# SH3_-_MCU.net
KiCad netlist of a schematic drawn in Altium Designer
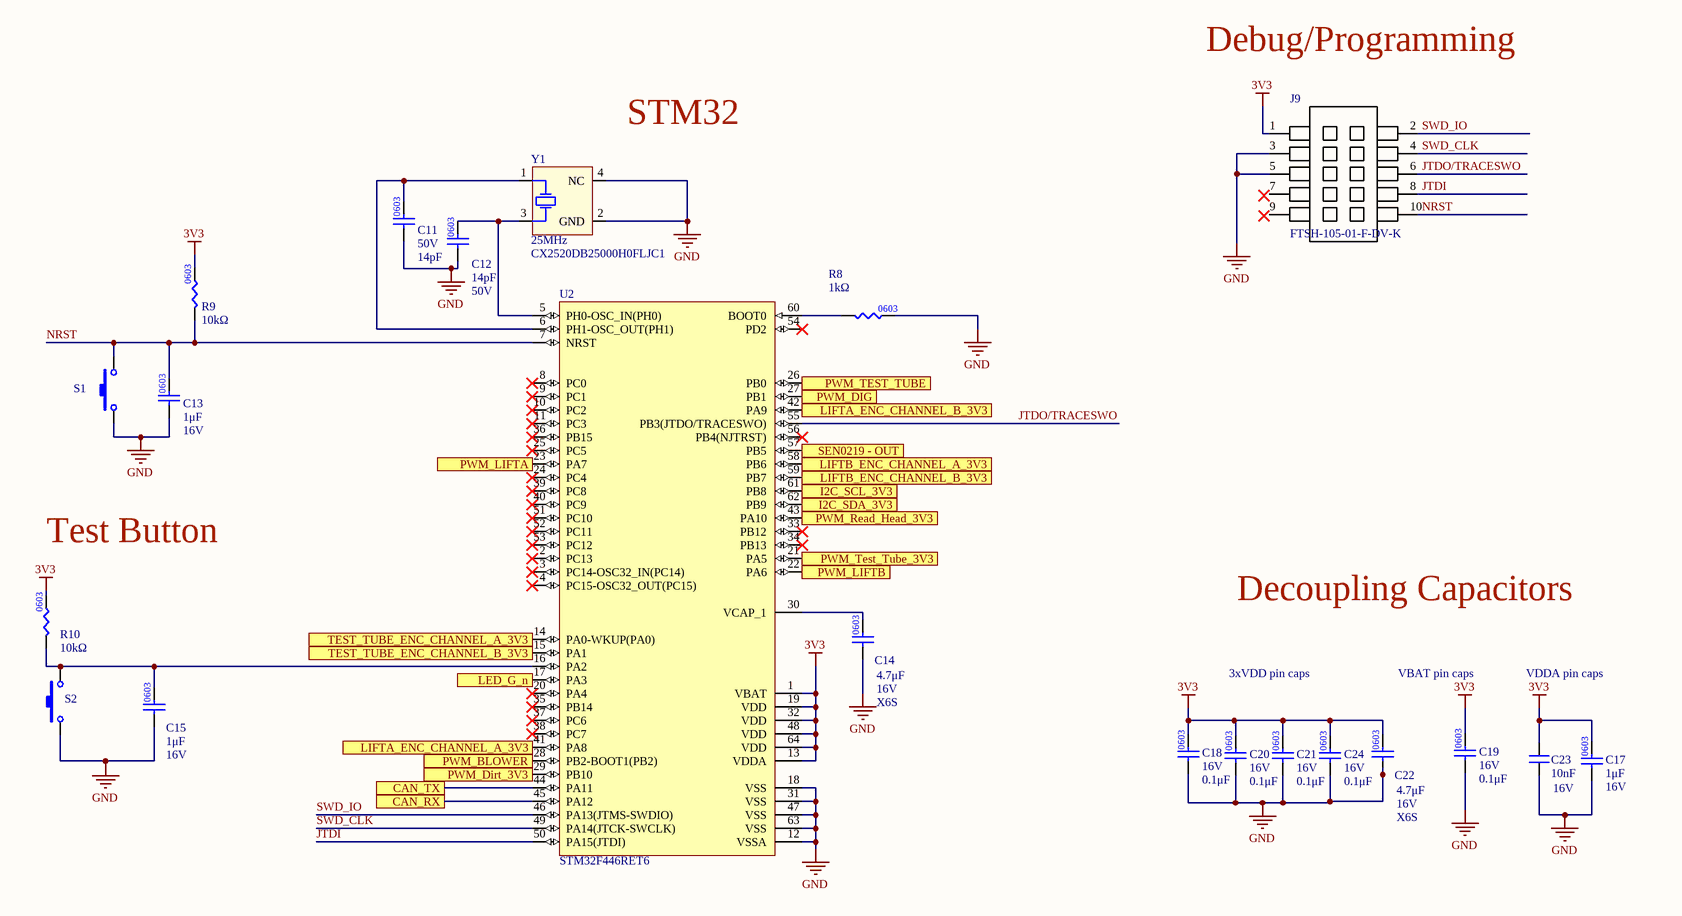
[diagram p0: SH3 - MCU.SchDoc]

(export (version "E")
  (design (tool "Eeschema 10.0.6"))
  (components
    (comp (ref "C11")
      (value "14pF")
      (footprint "CAP0603")
      (description "CAP CER 14PF 50V C0G/NP0 0603")
      (fields (field (name "VOLTAGE RATING") "50V") (field (name "Comment") "CAP_14pF_50V_0603"))
      (libsource (lib "UWRT_Schematic_Library_2020") (part "CAP_14pF_50V_0603"))
    )
    (comp (ref "C12")
      (value "14pF")
      (footprint "CAP0603")
      (description "CAP CER 14PF 50V C0G/NP0 0603")
      (fields (field (name "VOLTAGE RATING") "50V") (field (name "Comment") "CAP_14pF_50V_0603"))
      (libsource (lib "UWRT_Schematic_Library_2020") (part "CAP_14pF_50V_0603"))
    )
    (comp (ref "C13")
      (value "1μF")
      (footprint "CAP0603")
      (description "CAP CER 1UF 16V Y5V 0603")
      (fields (field (name "VOLTAGE RATING") "16V") (field (name "Comment") "CAP_1uF_16V_0603"))
      (libsource (lib "UWRT_Schematic_Library_2020") (part "CAP_1uF_16V_0603"))
    )
    (comp (ref "C14")
      (value "4.7μF")
      (footprint "CAP0603")
      (description "CAP CER 4.7UF 16V X6S 0603")
      (fields
        (field (name "DIELECTRIC") "X6S")
        (field (name "VOLTAGE RATING") "16V")
        (field (name "Comment") "CAP_4.7uF_16V_0603")
      )
      (libsource (lib "UWRT_Schematic_Library_2020") (part "CAP_4.7uF_16V_0603"))
    )
    (comp (ref "C15")
      (value "1μF")
      (footprint "CAP0603")
      (description "CAP CER 1UF 16V Y5V 0603")
      (fields (field (name "VOLTAGE RATING") "16V") (field (name "Comment") "CAP_1uF_16V_0603"))
      (libsource (lib "UWRT_Schematic_Library_2020") (part "CAP_1uF_16V_0603"))
    )
    (comp (ref "C17")
      (value "1μF")
      (footprint "CAP0603")
      (description "CAP CER 1UF 16V Y5V 0603")
      (fields (field (name "VOLTAGE RATING") "16V") (field (name "Comment") "CAP_1uF_16V_0603"))
      (libsource (lib "UWRT_Schematic_Library_2020") (part "CAP_1uF_16V_0603"))
    )
    (comp (ref "C18")
      (value "0.1μF")
      (footprint "CAP0603")
      (description "CAP CER 0.1UF 16V X7R 0603")
      (fields (field (name "VOLTAGE RATING") "16V") (field (name "Comment") "CAP_0.1uF_16V_0603"))
      (libsource (lib "UWRT_Schematic_Library_2020") (part "CAP_0.1uF_16V_0603"))
    )
    (comp (ref "C19")
      (value "0.1μF")
      (footprint "CAP0603")
      (description "CAP CER 0.1UF 16V X7R 0603")
      (fields (field (name "VOLTAGE RATING") "16V") (field (name "Comment") "CAP_0.1uF_16V_0603"))
      (libsource (lib "UWRT_Schematic_Library_2020") (part "CAP_0.1uF_16V_0603"))
    )
    (comp (ref "C20")
      (value "0.1μF")
      (footprint "CAP0603")
      (description "CAP CER 0.1UF 16V X7R 0603")
      (fields (field (name "VOLTAGE RATING") "16V") (field (name "Comment") "CAP_0.1uF_16V_0603"))
      (libsource (lib "UWRT_Schematic_Library_2020") (part "CAP_0.1uF_16V_0603"))
    )
    (comp (ref "C21")
      (value "0.1μF")
      (footprint "CAP0603")
      (description "CAP CER 0.1UF 16V X7R 0603")
      (fields (field (name "VOLTAGE RATING") "16V") (field (name "Comment") "CAP_0.1uF_16V_0603"))
      (libsource (lib "UWRT_Schematic_Library_2020") (part "CAP_0.1uF_16V_0603"))
    )
    (comp (ref "C22")
      (value "4.7μF")
      (footprint "CAP0603")
      (description "CAP CER 4.7UF 16V X6S 0603")
      (fields
        (field (name "DIELECTRIC") "X6S")
        (field (name "VOLTAGE RATING") "16V")
        (field (name "Comment") "CAP_4.7uF_16V_0603")
      )
      (libsource (lib "UWRT_Schematic_Library_2020") (part "CAP_4.7uF_16V_0603"))
    )
    (comp (ref "C23")
      (value "10nF")
      (footprint "CAP0603")
      (description "CAP CER 10000PF 16V X7R 0603")
      (fields (field (name "VOLTAGE RATING") "16V") (field (name "Comment") "CAP_10nF_0603"))
      (libsource (lib "UWRT_Schematic_Library_2020") (part "CAP_10nF_0603"))
    )
    (comp (ref "C24")
      (value "0.1μF")
      (footprint "CAP0603")
      (description "CAP CER 0.1UF 16V X7R 0603")
      (fields (field (name "VOLTAGE RATING") "16V") (field (name "Comment") "CAP_0.1uF_16V_0603"))
      (libsource (lib "UWRT_Schematic_Library_2020") (part "CAP_0.1uF_16V_0603"))
    )
    (comp (ref "J9")
      (value "CON_PROGRAMMING")
      (footprint "FTSH-105-01-F-DV-K-P-TR")
      (description "CONN HEADER SMD 10POS 1.27MM")
      (fields (field (name "MANUFACTURER PART NUMBER 1") "FTSH-105-01-F-DV-K"))
      (libsource (lib "UWRT_Schematic_Library_2020") (part "CON_PROGRAMMING"))
    )
    (comp (ref "R8")
      (value "1kΩ")
      (footprint "RES0603")
      (description "RES 1K OHM 5% 1/10W 0603")
      (fields (field (name "Comment") "RES_1kΩ_0603_5%"))
      (libsource (lib "UWRT_Schematic_Library_2020") (part "RES_1kΩ_0603_5%"))
    )
    (comp (ref "R9")
      (value "10kΩ")
      (footprint "RES0603")
      (description "RES 10K OHM 5% 1/10W 0603")
      (fields (field (name "Comment") "RES_10kΩ_0603_5%"))
      (libsource (lib "UWRT_Schematic_Library_2020") (part "RES_10kΩ_0603_5%"))
    )
    (comp (ref "R10")
      (value "10kΩ")
      (footprint "RES0603")
      (description "RES 10K OHM 5% 1/10W 0603")
      (fields (field (name "Comment") "RES_10kΩ_0603_5%"))
      (libsource (lib "UWRT_Schematic_Library_2020") (part "RES_10kΩ_0603_5%"))
    )
    (comp (ref "S1")
      (value "SW_TACTILE")
      (footprint "B3U-1000P")
      (description "SWITCH TACTILE SPST-NO 0.05A 12V")
      (libsource (lib "UWRT_Schematic_Library_2020") (part "SW_TACTILE"))
    )
    (comp (ref "S2")
      (value "SW_TACTILE")
      (footprint "B3U-1000P")
      (description "SWITCH TACTILE SPST-NO 0.05A 12V")
      (libsource (lib "UWRT_Schematic_Library_2020") (part "SW_TACTILE"))
    )
    (comp (ref "U2")
      (value "STM32F446RET6")
      (footprint "STM-LQFP64_L")
      (libsource (lib "UWRT_Schematic_Library_2020") (part "MCU_STM32F446RET6"))
    )
    (comp (ref "Y1")
      (value "CRYSTAL_25MHZ")
      (footprint "SOIC254P1016X440-4N")
      (description "CRYSTAL 25.0000MHZ 12PF SMD")
      (fields
        (field (name "FREQUENCY") "25MHz")
        (field (name "MANUFACTURER PART NUMBER 1") "CX2520DB25000H0FLJC1")
      )
      (libsource (lib "UWRT_Schematic_Library_2020") (part "CRYSTAL_25MHZ"))
    )
  )
  (nets
    (net (code "1") (name "/CAN_RX") (class "Default")
      (node (ref "U2") (pin "45") (pinfunction "PA12_45") (pintype "bidirectional"))
    )
    (net (code "2") (name "/CAN_TX") (class "Default")
      (node (ref "U2") (pin "44") (pinfunction "PA11_44") (pintype "bidirectional"))
    )
    (net (code "3") (name "/I2C_SCL_3V3") (class "Default")
      (node (ref "U2") (pin "61") (pinfunction "PB8_61") (pintype "bidirectional"))
    )
    (net (code "4") (name "/I2C_SDA_3V3") (class "Default")
      (node (ref "U2") (pin "62") (pinfunction "PB9_62") (pintype "bidirectional"))
    )
    (net (code "5") (name "/JTDI") (class "Default")
      (node (ref "J9") (pin "8") (pinfunction "8_8") (pintype "passive"))
      (node (ref "U2") (pin "50") (pinfunction "PA15(JTDI)_50") (pintype "bidirectional"))
    )
    (net (code "6") (name "/JTDO{slash}TRACESWO") (class "Default")
      (node (ref "J9") (pin "6") (pinfunction "6_6") (pintype "passive"))
      (node (ref "U2") (pin "55") (pinfunction "PB3(JTDO/TRACESWO)_55") (pintype "bidirectional"))
    )
    (net (code "7") (name "/LED_G_n") (class "Default")
      (node (ref "U2") (pin "17") (pinfunction "PA3_17") (pintype "bidirectional"))
    )
    (net (code "8") (name "/LIFTA_ENC_CHANNEL_A_3V3") (class "Default")
      (node (ref "U2") (pin "41") (pinfunction "PA8_41") (pintype "bidirectional"))
    )
    (net (code "9") (name "/LIFTA_ENC_CHANNEL_B_3V3") (class "Default")
      (node (ref "U2") (pin "42") (pinfunction "PA9_42") (pintype "bidirectional"))
    )
    (net (code "10") (name "/LIFTB_ENC_CHANNEL_A_3V3") (class "Default")
      (node (ref "U2") (pin "58") (pinfunction "PB6_58") (pintype "bidirectional"))
    )
    (net (code "11") (name "/LIFTB_ENC_CHANNEL_B_3V3") (class "Default")
      (node (ref "U2") (pin "59") (pinfunction "PB7_59") (pintype "bidirectional"))
    )
    (net (code "12") (name "/NRST") (class "Default")
      (node (ref "C13") (pin "2") (pinfunction "2_2") (pintype "passive"))
      (node (ref "J9") (pin "10") (pinfunction "10_10") (pintype "passive"))
      (node (ref "R9") (pin "1") (pinfunction "1_1") (pintype "passive"))
      (node (ref "S1") (pin "1") (pinfunction "1_1") (pintype "passive"))
      (node (ref "U2") (pin "7") (pinfunction "NRST_7") (pintype "bidirectional"))
    )
    (net (code "13") (name "/PWM_BLOWER") (class "Default")
      (node (ref "U2") (pin "28") (pinfunction "PB2-BOOT1(PB2)_28") (pintype "bidirectional"))
    )
    (net (code "14") (name "/PWM_DIG") (class "Default")
      (node (ref "U2") (pin "27") (pinfunction "PB1_27") (pintype "bidirectional"))
    )
    (net (code "15") (name "/PWM_Dirt_3V3") (class "Default")
      (node (ref "U2") (pin "29") (pinfunction "PB10_29") (pintype "bidirectional"))
    )
    (net (code "16") (name "/PWM_LIFTA") (class "Default")
      (node (ref "U2") (pin "23") (pinfunction "PA7_23") (pintype "bidirectional"))
    )
    (net (code "17") (name "/PWM_LIFTB") (class "Default")
      (node (ref "U2") (pin "22") (pinfunction "PA6_22") (pintype "bidirectional"))
    )
    (net (code "18") (name "/PWM_Read_Head_3V3") (class "Default")
      (node (ref "U2") (pin "43") (pinfunction "PA10_43") (pintype "bidirectional"))
    )
    (net (code "19") (name "/PWM_TEST_TUBE") (class "Default")
      (node (ref "U2") (pin "26") (pinfunction "PB0_26") (pintype "bidirectional"))
    )
    (net (code "20") (name "/PWM_Test_Tube_3V3") (class "Default")
      (node (ref "U2") (pin "21") (pinfunction "PA5_21") (pintype "bidirectional"))
    )
    (net (code "21") (name "/SEN0219 - OUT") (class "Default")
      (node (ref "U2") (pin "57") (pinfunction "PB5_57") (pintype "bidirectional"))
    )
    (net (code "22") (name "/SWD_CLK") (class "Default")
      (node (ref "J9") (pin "4") (pinfunction "4_4") (pintype "passive"))
      (node (ref "U2") (pin "49") (pinfunction "PA14(JTCK-SWCLK)_49") (pintype "bidirectional"))
    )
    (net (code "23") (name "/SWD_IO") (class "Default")
      (node (ref "J9") (pin "2") (pinfunction "2_2") (pintype "passive"))
      (node (ref "U2") (pin "46") (pinfunction "PA13(JTMS-SWDIO)_46") (pintype "bidirectional"))
    )
    (net (code "24") (name "/TEST_TUBE_ENC_CHANNEL_A_3V3") (class "Default")
      (node (ref "U2") (pin "14") (pinfunction "PA0-WKUP(PA0)_14") (pintype "bidirectional"))
    )
    (net (code "25") (name "/TEST_TUBE_ENC_CHANNEL_B_3V3") (class "Default")
      (node (ref "U2") (pin "15") (pinfunction "PA1_15") (pintype "bidirectional"))
    )
    (net (code "26") (name "3V3") (class "Default")
      (node (ref "C17") (pin "2") (pinfunction "2_2") (pintype "passive"))
      (node (ref "C18") (pin "2") (pinfunction "2_2") (pintype "passive"))
      (node (ref "C19") (pin "2") (pinfunction "2_2") (pintype "passive"))
      (node (ref "C20") (pin "2") (pinfunction "2_2") (pintype "passive"))
      (node (ref "C21") (pin "2") (pinfunction "2_2") (pintype "passive"))
      (node (ref "C22") (pin "2") (pinfunction "2_2") (pintype "passive"))
      (node (ref "C23") (pin "2") (pinfunction "2_2") (pintype "passive"))
      (node (ref "C24") (pin "2") (pinfunction "2_2") (pintype "passive"))
      (node (ref "J9") (pin "1") (pinfunction "1_1") (pintype "passive"))
      (node (ref "R10") (pin "2") (pinfunction "2_2") (pintype "passive"))
      (node (ref "R9") (pin "2") (pinfunction "2_2") (pintype "passive"))
      (node (ref "U2") (pin "1") (pinfunction "VBAT_1") (pintype "power_in"))
      (node (ref "U2") (pin "13") (pinfunction "VDDA_13") (pintype "power_in"))
      (node (ref "U2") (pin "19") (pinfunction "VDD_19") (pintype "power_in"))
      (node (ref "U2") (pin "32") (pinfunction "VDD_32") (pintype "power_in"))
      (node (ref "U2") (pin "48") (pinfunction "VDD_48") (pintype "power_in"))
      (node (ref "U2") (pin "64") (pinfunction "VDD_64") (pintype "power_in"))
    )
    (net (code "27") (name "GND") (class "Default")
      (node (ref "C11") (pin "1") (pinfunction "1_1") (pintype "passive"))
      (node (ref "C12") (pin "1") (pinfunction "1_1") (pintype "passive"))
      (node (ref "C13") (pin "1") (pinfunction "1_1") (pintype "passive"))
      (node (ref "C14") (pin "1") (pinfunction "1_1") (pintype "passive"))
      (node (ref "C15") (pin "1") (pinfunction "1_1") (pintype "passive"))
      (node (ref "C17") (pin "1") (pinfunction "1_1") (pintype "passive"))
      (node (ref "C18") (pin "1") (pinfunction "1_1") (pintype "passive"))
      (node (ref "C19") (pin "1") (pinfunction "1_1") (pintype "passive"))
      (node (ref "C20") (pin "1") (pinfunction "1_1") (pintype "passive"))
      (node (ref "C21") (pin "1") (pinfunction "1_1") (pintype "passive"))
      (node (ref "C22") (pin "1") (pinfunction "1_1") (pintype "passive"))
      (node (ref "C23") (pin "1") (pinfunction "1_1") (pintype "passive"))
      (node (ref "C24") (pin "1") (pinfunction "1_1") (pintype "passive"))
      (node (ref "J9") (pin "3") (pinfunction "3_3") (pintype "passive"))
      (node (ref "J9") (pin "5") (pinfunction "5_5") (pintype "passive"))
      (node (ref "R8") (pin "2") (pinfunction "2_2") (pintype "passive"))
      (node (ref "S1") (pin "2") (pinfunction "2_2") (pintype "passive"))
      (node (ref "S2") (pin "1") (pinfunction "1_1") (pintype "passive"))
      (node (ref "U2") (pin "12") (pinfunction "VSSA_12") (pintype "power_in"))
      (node (ref "U2") (pin "18") (pinfunction "VSS_18") (pintype "power_in"))
      (node (ref "U2") (pin "31") (pinfunction "VSS_31") (pintype "power_in"))
      (node (ref "U2") (pin "47") (pinfunction "VSS_47") (pintype "power_in"))
      (node (ref "U2") (pin "63") (pinfunction "VSS_63") (pintype "power_in"))
      (node (ref "Y1") (pin "2") (pinfunction "GND_2") (pintype "power_in"))
      (node (ref "Y1") (pin "4") (pinfunction "NC_4") (pintype "passive"))
    )
    (net (code "28") (name "Net-(U2-BOOT0)") (class "Default")
      (node (ref "R8") (pin "1") (pinfunction "1_1") (pintype "passive"))
      (node (ref "U2") (pin "60") (pinfunction "BOOT0_60") (pintype "input"))
    )
    (net (code "29") (name "Net-(U2-PA2)") (class "Default")
      (node (ref "C15") (pin "2") (pinfunction "2_2") (pintype "passive"))
      (node (ref "R10") (pin "1") (pinfunction "1_1") (pintype "passive"))
      (node (ref "S2") (pin "2") (pinfunction "2_2") (pintype "passive"))
      (node (ref "U2") (pin "16") (pinfunction "PA2_16") (pintype "bidirectional"))
    )
    (net (code "30") (name "Net-(U2-PH0-OSC_IN(PH0))") (class "Default")
      (node (ref "C12") (pin "2") (pinfunction "2_2") (pintype "passive"))
      (node (ref "U2") (pin "5") (pinfunction "PH0-OSC_IN(PH0)_5") (pintype "bidirectional"))
      (node (ref "Y1") (pin "3") (pinfunction "HOT_3") (pintype "passive"))
    )
    (net (code "31") (name "Net-(U2-PH1-OSC_OUT(PH1))") (class "Default")
      (node (ref "C11") (pin "2") (pinfunction "2_2") (pintype "passive"))
      (node (ref "U2") (pin "6") (pinfunction "PH1-OSC_OUT(PH1)_6") (pintype "bidirectional"))
      (node (ref "Y1") (pin "1") (pinfunction "HOT_1") (pintype "passive"))
    )
    (net (code "32") (name "Net-(U2-VCAP_1)") (class "Default")
      (node (ref "C14") (pin "2") (pinfunction "2_2") (pintype "passive"))
      (node (ref "U2") (pin "30") (pinfunction "VCAP_1_30") (pintype "passive"))
    )
    (net (code "33") (name "unconnected-(J9-Pad7)") (class "Default")
      (node (ref "J9") (pin "7") (pinfunction "7_7") (pintype "passive"))
    )
    (net (code "34") (name "unconnected-(J9-Pad9)") (class "Default")
      (node (ref "J9") (pin "9") (pinfunction "9_9") (pintype "passive"))
    )
    (net (code "35") (name "unconnected-(U2-PA4-Pad20)") (class "Default")
      (node (ref "U2") (pin "20") (pinfunction "PA4_20") (pintype "bidirectional+no_connect"))
    )
    (net (code "36") (name "unconnected-(U2-PB4(NJTRST)-Pad56)") (class "Default")
      (node (ref "U2") (pin "56") (pinfunction "PB4(NJTRST)_56") (pintype "bidirectional+no_connect"))
    )
    (net (code "37") (name "unconnected-(U2-PB12-Pad33)") (class "Default")
      (node (ref "U2") (pin "33") (pinfunction "PB12_33") (pintype "bidirectional+no_connect"))
    )
    (net (code "38") (name "unconnected-(U2-PB13-Pad34)") (class "Default")
      (node (ref "U2") (pin "34") (pinfunction "PB13_34") (pintype "bidirectional+no_connect"))
    )
    (net (code "39") (name "unconnected-(U2-PB14-Pad35)") (class "Default")
      (node (ref "U2") (pin "35") (pinfunction "PB14_35") (pintype "bidirectional+no_connect"))
    )
    (net (code "40") (name "unconnected-(U2-PB15-Pad36)") (class "Default")
      (node (ref "U2") (pin "36") (pinfunction "PB15_36") (pintype "bidirectional+no_connect"))
    )
    (net (code "41") (name "unconnected-(U2-PC0-Pad8)") (class "Default")
      (node (ref "U2") (pin "8") (pinfunction "PC0_8") (pintype "bidirectional+no_connect"))
    )
    (net (code "42") (name "unconnected-(U2-PC1-Pad9)") (class "Default")
      (node (ref "U2") (pin "9") (pinfunction "PC1_9") (pintype "bidirectional+no_connect"))
    )
    (net (code "43") (name "unconnected-(U2-PC2-Pad10)") (class "Default")
      (node (ref "U2") (pin "10") (pinfunction "PC2_10") (pintype "bidirectional+no_connect"))
    )
    (net (code "44") (name "unconnected-(U2-PC3-Pad11)") (class "Default")
      (node (ref "U2") (pin "11") (pinfunction "PC3_11") (pintype "bidirectional+no_connect"))
    )
    (net (code "45") (name "unconnected-(U2-PC4-Pad24)") (class "Default")
      (node (ref "U2") (pin "24") (pinfunction "PC4_24") (pintype "bidirectional+no_connect"))
    )
    (net (code "46") (name "unconnected-(U2-PC5-Pad25)") (class "Default")
      (node (ref "U2") (pin "25") (pinfunction "PC5_25") (pintype "bidirectional+no_connect"))
    )
    (net (code "47") (name "unconnected-(U2-PC6-Pad37)") (class "Default")
      (node (ref "U2") (pin "37") (pinfunction "PC6_37") (pintype "bidirectional+no_connect"))
    )
    (net (code "48") (name "unconnected-(U2-PC7-Pad38)") (class "Default")
      (node (ref "U2") (pin "38") (pinfunction "PC7_38") (pintype "bidirectional+no_connect"))
    )
    (net (code "49") (name "unconnected-(U2-PC8-Pad39)") (class "Default")
      (node (ref "U2") (pin "39") (pinfunction "PC8_39") (pintype "bidirectional+no_connect"))
    )
    (net (code "50") (name "unconnected-(U2-PC9-Pad40)") (class "Default")
      (node (ref "U2") (pin "40") (pinfunction "PC9_40") (pintype "bidirectional+no_connect"))
    )
    (net (code "51") (name "unconnected-(U2-PC10-Pad51)") (class "Default")
      (node (ref "U2") (pin "51") (pinfunction "PC10_51") (pintype "bidirectional+no_connect"))
    )
    (net (code "52") (name "unconnected-(U2-PC11-Pad52)") (class "Default")
      (node (ref "U2") (pin "52") (pinfunction "PC11_52") (pintype "bidirectional+no_connect"))
    )
    (net (code "53") (name "unconnected-(U2-PC12-Pad53)") (class "Default")
      (node (ref "U2") (pin "53") (pinfunction "PC12_53") (pintype "bidirectional+no_connect"))
    )
    (net (code "54") (name "unconnected-(U2-PC13-Pad2)") (class "Default")
      (node (ref "U2") (pin "2") (pinfunction "PC13_2") (pintype "bidirectional+no_connect"))
    )
    (net (code "55") (name "unconnected-(U2-PC14-OSC32_IN(PC14)-Pad3)") (class "Default")
      (node (ref "U2") (pin "3") (pinfunction "PC14-OSC32_IN(PC14)_3") (pintype "bidirectional+no_connect"))
    )
    (net (code "56") (name "unconnected-(U2-PC15-OSC32_OUT(PC15)-Pad4)") (class "Default")
      (node (ref "U2") (pin "4") (pinfunction "PC15-OSC32_OUT(PC15)_4") (pintype "bidirectional+no_connect"))
    )
    (net (code "57") (name "unconnected-(U2-PD2-Pad54)") (class "Default")
      (node (ref "U2") (pin "54") (pinfunction "PD2_54") (pintype "bidirectional+no_connect"))
    )
  )
)
